# Power_Dev_revA_3.net
KiCad netlist of a schematic drawn in EAGLE
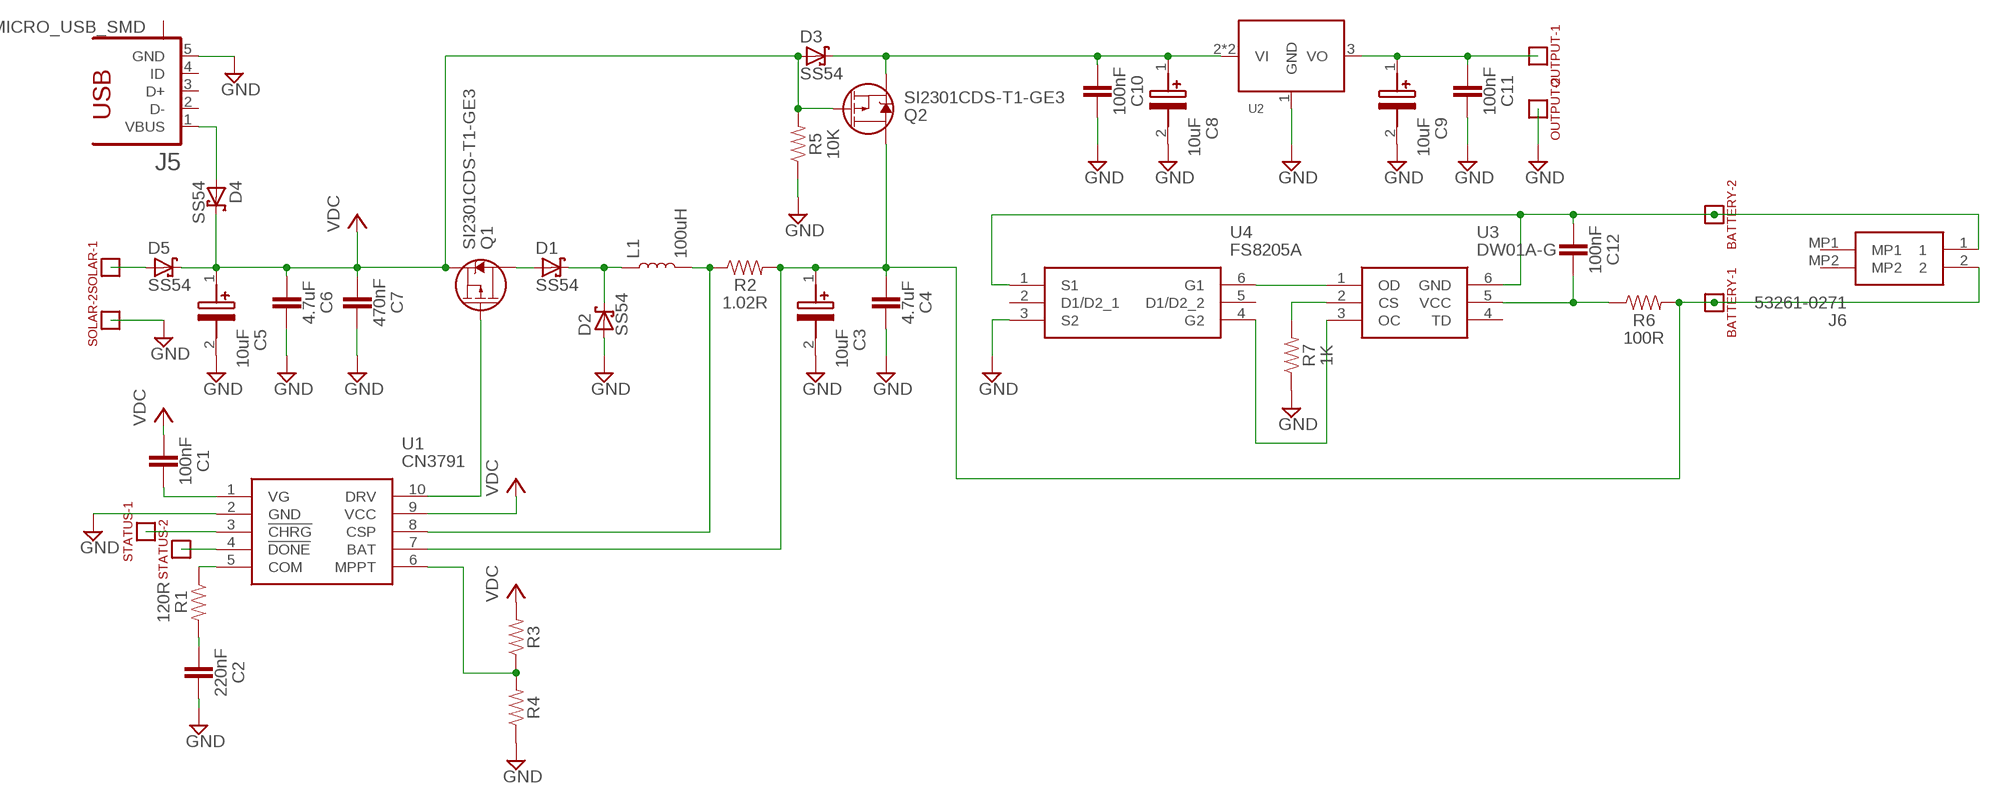
[diagram p0: schematic, sheet 1]

(export (version "E")
  (design (tool "Eeschema 10.0.6"))
  (components
    (comp (ref "BATTERY")
      (value "HEADER_2PIN")
      (footprint "eagle-import:HEADER_2PIN")
      (libsource (lib "eagle-import") (part "HEADER_2PIN"))
    )
    (comp (ref "C1")
      (value "100nF")
      (footprint "eagle-import:0402")
      (libsource (lib "eagle-import") (part "C_0402"))
    )
    (comp (ref "C2")
      (value "220nF")
      (footprint "eagle-import:0603")
      (libsource (lib "eagle-import") (part "C_0603"))
    )
    (comp (ref "C3")
      (value "10uF")
      (footprint "eagle-import:6MM_SMD_ECAP")
      (libsource (lib "eagle-import") (part "6.3MM_SMD_ECAP"))
    )
    (comp (ref "C4")
      (value "4.7uF")
      (footprint "eagle-import:1206")
      (libsource (lib "eagle-import") (part "C_1206"))
    )
    (comp (ref "C5")
      (value "10uF")
      (footprint "eagle-import:6MM_SMD_ECAP")
      (libsource (lib "eagle-import") (part "6.3MM_SMD_ECAP"))
    )
    (comp (ref "C6")
      (value "4.7uF")
      (footprint "eagle-import:1206")
      (libsource (lib "eagle-import") (part "C_1206"))
    )
    (comp (ref "C7")
      (value "470nF")
      (footprint "eagle-import:0805")
      (libsource (lib "eagle-import") (part "C_0805"))
    )
    (comp (ref "C8")
      (value "10uF")
      (footprint "eagle-import:6MM_SMD_ECAP")
      (libsource (lib "eagle-import") (part "6.3MM_SMD_ECAP"))
    )
    (comp (ref "C9")
      (value "10uF")
      (footprint "eagle-import:6MM_SMD_ECAP")
      (libsource (lib "eagle-import") (part "6.3MM_SMD_ECAP"))
    )
    (comp (ref "C10")
      (value "100nF")
      (footprint "eagle-import:0402")
      (libsource (lib "eagle-import") (part "C_0402"))
    )
    (comp (ref "C11")
      (value "100nF")
      (footprint "eagle-import:0402")
      (libsource (lib "eagle-import") (part "C_0402"))
    )
    (comp (ref "C12")
      (value "100nF")
      (footprint "eagle-import:0402")
      (libsource (lib "eagle-import") (part "C_0402"))
    )
    (comp (ref "D1")
      (value "SS54")
      (footprint "eagle-import:SMA(DO-214AC)")
      (libsource (lib "eagle-import") (part "DIODE_SCHOTTKY_SMA"))
    )
    (comp (ref "D2")
      (value "SS54")
      (footprint "eagle-import:SMA(DO-214AC)")
      (libsource (lib "eagle-import") (part "DIODE_SCHOTTKY_SMA"))
    )
    (comp (ref "D3")
      (value "SS54")
      (footprint "eagle-import:SMA(DO-214AC)")
      (libsource (lib "eagle-import") (part "DIODE_SCHOTTKY_SMA"))
    )
    (comp (ref "D4")
      (value "SS54")
      (footprint "eagle-import:SMA(DO-214AC)")
      (libsource (lib "eagle-import") (part "DIODE_SCHOTTKY_SMA"))
    )
    (comp (ref "D5")
      (value "SS54")
      (footprint "eagle-import:SMA(DO-214AC)")
      (libsource (lib "eagle-import") (part "DIODE_SCHOTTKY_SMA"))
    )
    (comp (ref "J5")
      (value "MICRO_USB_SMD")
      (footprint "eagle-import:10118192-0002LF")
      (libsource (lib "eagle-import") (part "MICRO_USB_SMD"))
    )
    (comp (ref "J6")
      (value "53261-0271")
      (footprint "eagle-import:532610271")
      (fields (field (name "MOUSER_PART_NUMBER") "538-53261-0271"))
      (libsource (lib "eagle-import") (part "53261-0271"))
    )
    (comp (ref "L1")
      (value "100uH")
      (footprint "eagle-import:L_SMD,7X7.8MM")
      (libsource (lib "eagle-import") (part "L_SMD,7X7.8MM"))
    )
    (comp (ref "OUTPUT")
      (value "HEADER_2PIN")
      (footprint "eagle-import:HEADER_2PIN")
      (libsource (lib "eagle-import") (part "HEADER_2PIN"))
    )
    (comp (ref "Q1")
      (value "SI2301CDS-T1-GE3")
      (footprint "eagle-import:SOT-23")
      (libsource (lib "eagle-import") (part "MOSFET_P_SOT23"))
    )
    (comp (ref "Q2")
      (value "SI2301CDS-T1-GE3")
      (footprint "eagle-import:SOT-23")
      (libsource (lib "eagle-import") (part "MOSFET_P_SOT23"))
    )
    (comp (ref "R1")
      (value "120R")
      (footprint "eagle-import:0805")
      (libsource (lib "eagle-import") (part "R_0805"))
    )
    (comp (ref "R2")
      (value "1.02R")
      (footprint "eagle-import:1206")
      (libsource (lib "eagle-import") (part "R_1206"))
    )
    (comp (ref "R3")
      (value "RESISTOR_TH")
      (footprint "eagle-import:RESISTOR_TH")
      (libsource (lib "eagle-import") (part "RESISTOR_TH"))
    )
    (comp (ref "R4")
      (value "RESISTOR_TH")
      (footprint "eagle-import:RESISTOR_TH")
      (libsource (lib "eagle-import") (part "RESISTOR_TH"))
    )
    (comp (ref "R5")
      (value "10K")
      (footprint "eagle-import:0402")
      (libsource (lib "eagle-import") (part "R_0402"))
    )
    (comp (ref "R6")
      (value "100R")
      (footprint "eagle-import:0402")
      (libsource (lib "eagle-import") (part "R_0402"))
    )
    (comp (ref "R7")
      (value "1K")
      (footprint "eagle-import:0402")
      (libsource (lib "eagle-import") (part "R_0402"))
    )
    (comp (ref "SOLAR")
      (value "HEADER_2PIN")
      (footprint "eagle-import:HEADER_2PIN")
      (libsource (lib "eagle-import") (part "HEADER_2PIN"))
    )
    (comp (ref "STATUS")
      (value "HEADER_2PIN")
      (footprint "eagle-import:HEADER_2PIN")
      (libsource (lib "eagle-import") (part "HEADER_2PIN"))
    )
    (comp (ref "U1")
      (value "CN3791")
      (footprint "eagle-import:SOP100P600X175-10N")
      (libsource (lib "eagle-import") (part "CN3791"))
    )
    (comp (ref "U2")
      (value "LDO_SOT89")
      (footprint "eagle-import:SOT-89-3")
      (libsource (lib "eagle-import") (part "LDO_SOT89"))
    )
    (comp (ref "U3")
      (value "DW01A-G")
      (footprint "eagle-import:SOT95P280X135-6N")
      (libsource (lib "eagle-import") (part "DW01A-G"))
    )
    (comp (ref "U4")
      (value "FS8205A")
      (footprint "eagle-import:SOT95P280X125-6N")
      (libsource (lib "eagle-import") (part "FS8205A"))
    )
  )
  (nets
    (net (code "1") (name "GND") (class "Default")
      (node (ref "C10") (pin "2") (pinfunction "2_2") (pintype "passive"))
      (node (ref "C11") (pin "2") (pinfunction "2_2") (pintype "passive"))
      (node (ref "C2") (pin "2") (pinfunction "2_2") (pintype "passive"))
      (node (ref "C3") (pin "2") (pinfunction "-_2") (pintype "bidirectional"))
      (node (ref "C4") (pin "2") (pinfunction "2_2") (pintype "passive"))
      (node (ref "C5") (pin "2") (pinfunction "-_2") (pintype "bidirectional"))
      (node (ref "C6") (pin "2") (pinfunction "2_2") (pintype "passive"))
      (node (ref "C7") (pin "2") (pinfunction "2_2") (pintype "passive"))
      (node (ref "C8") (pin "2") (pinfunction "-_2") (pintype "bidirectional"))
      (node (ref "C9") (pin "2") (pinfunction "-_2") (pintype "bidirectional"))
      (node (ref "D2") (pin "2") (pinfunction "A_2") (pintype "passive"))
      (node (ref "J5") (pin "5") (pinfunction "GND_5") (pintype "passive"))
      (node (ref "OUTPUT") (pin "P$2") (pinfunction "P$1_P$2") (pintype "bidirectional"))
      (node (ref "R4") (pin "P$1") (pinfunction "1_P$1") (pintype "passive"))
      (node (ref "R5") (pin "1") (pinfunction "1_1") (pintype "passive"))
      (node (ref "R7") (pin "1") (pinfunction "1_1") (pintype "passive"))
      (node (ref "SOLAR") (pin "P$2") (pinfunction "P$1_P$2") (pintype "bidirectional"))
      (node (ref "U1") (pin "2") (pinfunction "GND_2") (pintype "bidirectional"))
      (node (ref "U2") (pin "1") (pinfunction "GND_1") (pintype "bidirectional"))
      (node (ref "U4") (pin "3") (pinfunction "S2_3") (pintype "bidirectional"))
    )
    (net (code "2") (name "Net-(BATTERYB-P$1)") (class "Default")
      (node (ref "BATTERY") (pin "P$2") (pinfunction "P$1_P$2") (pintype "bidirectional"))
      (node (ref "C12") (pin "1") (pinfunction "1_1") (pintype "passive"))
      (node (ref "J6") (pin "1") (pinfunction "1_1") (pintype "bidirectional"))
      (node (ref "U3") (pin "6") (pinfunction "GND_6") (pintype "bidirectional"))
      (node (ref "U4") (pin "1") (pinfunction "S1_1") (pintype "bidirectional"))
    )
    (net (code "3") (name "Net-(C2-Pad1)") (class "Default")
      (node (ref "C2") (pin "1") (pinfunction "1_1") (pintype "passive"))
      (node (ref "R1") (pin "2") (pinfunction "2_2") (pintype "passive"))
    )
    (net (code "4") (name "Net-(C3-+)") (class "Default")
      (node (ref "BATTERY") (pin "P$1") (pinfunction "P$1_P$1") (pintype "bidirectional"))
      (node (ref "C3") (pin "1") (pinfunction "+_1") (pintype "bidirectional"))
      (node (ref "C4") (pin "1") (pinfunction "1_1") (pintype "passive"))
      (node (ref "J6") (pin "2") (pinfunction "2_2") (pintype "bidirectional"))
      (node (ref "Q2") (pin "3") (pinfunction "D_3") (pintype "bidirectional"))
      (node (ref "R2") (pin "2") (pinfunction "2_2") (pintype "passive"))
      (node (ref "R6") (pin "2") (pinfunction "2_2") (pintype "passive"))
      (node (ref "U1") (pin "7") (pinfunction "BAT_7") (pintype "bidirectional"))
    )
    (net (code "5") (name "Net-(C8-+)") (class "Default")
      (node (ref "C10") (pin "1") (pinfunction "1_1") (pintype "passive"))
      (node (ref "C8") (pin "1") (pinfunction "+_1") (pintype "bidirectional"))
      (node (ref "D3") (pin "1") (pinfunction "C_1") (pintype "passive"))
      (node (ref "Q2") (pin "2") (pinfunction "S_2") (pintype "bidirectional"))
      (node (ref "U2") (pin "2") (pinfunction "VI_2") (pintype "bidirectional"))
      (node (ref "U2") (pin "4") (pinfunction "VI_4") (pintype "bidirectional"))
    )
    (net (code "6") (name "Net-(C9-+)") (class "Default")
      (node (ref "C11") (pin "1") (pinfunction "1_1") (pintype "passive"))
      (node (ref "C9") (pin "1") (pinfunction "+_1") (pintype "bidirectional"))
      (node (ref "OUTPUT") (pin "P$1") (pinfunction "P$1_P$1") (pintype "bidirectional"))
      (node (ref "U2") (pin "3") (pinfunction "VO_3") (pintype "bidirectional"))
    )
    (net (code "7") (name "Net-(D1-A)") (class "Default")
      (node (ref "D1") (pin "2") (pinfunction "A_2") (pintype "passive"))
      (node (ref "Q1") (pin "3") (pinfunction "D_3") (pintype "bidirectional"))
    )
    (net (code "8") (name "Net-(D1-C)") (class "Default")
      (node (ref "D1") (pin "1") (pinfunction "C_1") (pintype "passive"))
      (node (ref "D2") (pin "1") (pinfunction "C_1") (pintype "passive"))
      (node (ref "L1") (pin "P$1") (pinfunction "1_P$1") (pintype "passive"))
    )
    (net (code "9") (name "Net-(D4-A)") (class "Default")
      (node (ref "D4") (pin "2") (pinfunction "A_2") (pintype "passive"))
      (node (ref "J5") (pin "1") (pinfunction "VBUS_1") (pintype "passive"))
    )
    (net (code "10") (name "Net-(D5-A)") (class "Default")
      (node (ref "D5") (pin "2") (pinfunction "A_2") (pintype "passive"))
      (node (ref "SOLAR") (pin "P$1") (pinfunction "P$1_P$1") (pintype "bidirectional"))
    )
    (net (code "11") (name "Net-(L1-2)") (class "Default")
      (node (ref "L1") (pin "P$2") (pinfunction "2_P$2") (pintype "passive"))
      (node (ref "R2") (pin "1") (pinfunction "1_1") (pintype "passive"))
      (node (ref "U1") (pin "8") (pinfunction "CSP_8") (pintype "bidirectional"))
    )
    (net (code "12") (name "Net-(Q1-G)") (class "Default")
      (node (ref "Q1") (pin "1") (pinfunction "G_1") (pintype "bidirectional"))
      (node (ref "U1") (pin "10") (pinfunction "DRV_10") (pintype "bidirectional"))
    )
    (net (code "13") (name "Net-(R3-1)") (class "Default")
      (node (ref "R3") (pin "P$1") (pinfunction "1_P$1") (pintype "passive"))
      (node (ref "R4") (pin "P$2") (pinfunction "2_P$2") (pintype "passive"))
      (node (ref "U1") (pin "6") (pinfunction "MPPT_6") (pintype "bidirectional"))
    )
    (net (code "14") (name "Net-(STATUSB-P$1)") (class "Default")
      (node (ref "STATUS") (pin "P$2") (pinfunction "P$1_P$2") (pintype "bidirectional"))
      (node (ref "U1") (pin "4") (pinfunction "~{DONE}_4") (pintype "bidirectional"))
    )
    (net (code "15") (name "Net-(U1-COM)") (class "Default")
      (node (ref "R1") (pin "1") (pinfunction "1_1") (pintype "passive"))
      (node (ref "U1") (pin "5") (pinfunction "COM_5") (pintype "bidirectional"))
    )
    (net (code "16") (name "Net-(U1-VG)") (class "Default")
      (node (ref "C1") (pin "2") (pinfunction "2_2") (pintype "passive"))
      (node (ref "U1") (pin "1") (pinfunction "VG_1") (pintype "bidirectional"))
    )
    (net (code "17") (name "Net-(U1-~{CHRG})") (class "Default")
      (node (ref "STATUS") (pin "P$1") (pinfunction "P$1_P$1") (pintype "bidirectional"))
      (node (ref "U1") (pin "3") (pinfunction "~{CHRG}_3") (pintype "bidirectional"))
    )
    (net (code "18") (name "Net-(U3-CS)") (class "Default")
      (node (ref "R7") (pin "2") (pinfunction "2_2") (pintype "passive"))
      (node (ref "U3") (pin "2") (pinfunction "CS_2") (pintype "bidirectional"))
    )
    (net (code "19") (name "Net-(U3-OC)") (class "Default")
      (node (ref "U3") (pin "3") (pinfunction "OC_3") (pintype "bidirectional"))
      (node (ref "U4") (pin "4") (pinfunction "G2_4") (pintype "bidirectional"))
    )
    (net (code "20") (name "Net-(U3-OD)") (class "Default")
      (node (ref "U3") (pin "1") (pinfunction "OD_1") (pintype "bidirectional"))
      (node (ref "U4") (pin "6") (pinfunction "G1_6") (pintype "bidirectional"))
    )
    (net (code "21") (name "Net-(U3-VCC)") (class "Default")
      (node (ref "C12") (pin "2") (pinfunction "2_2") (pintype "passive"))
      (node (ref "R6") (pin "1") (pinfunction "1_1") (pintype "passive"))
      (node (ref "U3") (pin "5") (pinfunction "VCC_5") (pintype "bidirectional"))
    )
    (net (code "22") (name "VDC") (class "Default")
      (node (ref "C1") (pin "1") (pinfunction "1_1") (pintype "passive"))
      (node (ref "C5") (pin "1") (pinfunction "+_1") (pintype "bidirectional"))
      (node (ref "C6") (pin "1") (pinfunction "1_1") (pintype "passive"))
      (node (ref "C7") (pin "1") (pinfunction "1_1") (pintype "passive"))
      (node (ref "D3") (pin "2") (pinfunction "A_2") (pintype "passive"))
      (node (ref "D4") (pin "1") (pinfunction "C_1") (pintype "passive"))
      (node (ref "D5") (pin "1") (pinfunction "C_1") (pintype "passive"))
      (node (ref "Q1") (pin "2") (pinfunction "S_2") (pintype "bidirectional"))
      (node (ref "Q2") (pin "1") (pinfunction "G_1") (pintype "bidirectional"))
      (node (ref "R3") (pin "P$2") (pinfunction "2_P$2") (pintype "passive"))
      (node (ref "R5") (pin "2") (pinfunction "2_2") (pintype "passive"))
      (node (ref "U1") (pin "9") (pinfunction "VCC_9") (pintype "bidirectional"))
    )
    (net (code "23") (name "unconnected-(J5-D+-Pad3)") (class "Default")
      (node (ref "J5") (pin "3") (pinfunction "D+_3") (pintype "passive"))
    )
    (net (code "24") (name "unconnected-(J5-D--Pad2)") (class "Default")
      (node (ref "J5") (pin "2") (pinfunction "D-_2") (pintype "passive"))
    )
    (net (code "25") (name "unconnected-(J5-ID-Pad4)") (class "Default")
      (node (ref "J5") (pin "4") (pinfunction "ID_4") (pintype "passive"))
    )
    (net (code "26") (name "unconnected-(J5-PadS1)") (class "Default")
      (node (ref "J5") (pin "S1") (pinfunction "S1_S1") (pintype "passive"))
    )
    (net (code "27") (name "unconnected-(J6-PadMP1)") (class "Default")
      (node (ref "J6") (pin "MP1") (pinfunction "MP1_MP1") (pintype "bidirectional"))
    )
    (net (code "28") (name "unconnected-(J6-PadMP2)") (class "Default")
      (node (ref "J6") (pin "MP2") (pinfunction "MP2_MP2") (pintype "bidirectional"))
    )
    (net (code "29") (name "unconnected-(U3-TD-Pad4)") (class "Default")
      (node (ref "U3") (pin "4") (pinfunction "TD_4") (pintype "bidirectional"))
    )
    (net (code "30") (name "unconnected-(U4-D1{slash}D2_1-Pad2)") (class "Default")
      (node (ref "U4") (pin "2") (pinfunction "D1/D2_1_2") (pintype "bidirectional"))
    )
    (net (code "31") (name "unconnected-(U4-D1{slash}D2_2-Pad5)") (class "Default")
      (node (ref "U4") (pin "5") (pinfunction "D1/D2_2_5") (pintype "bidirectional"))
    )
  )
)
